# connectors.net
KiCad netlist of a schematic drawn in Altium Designer
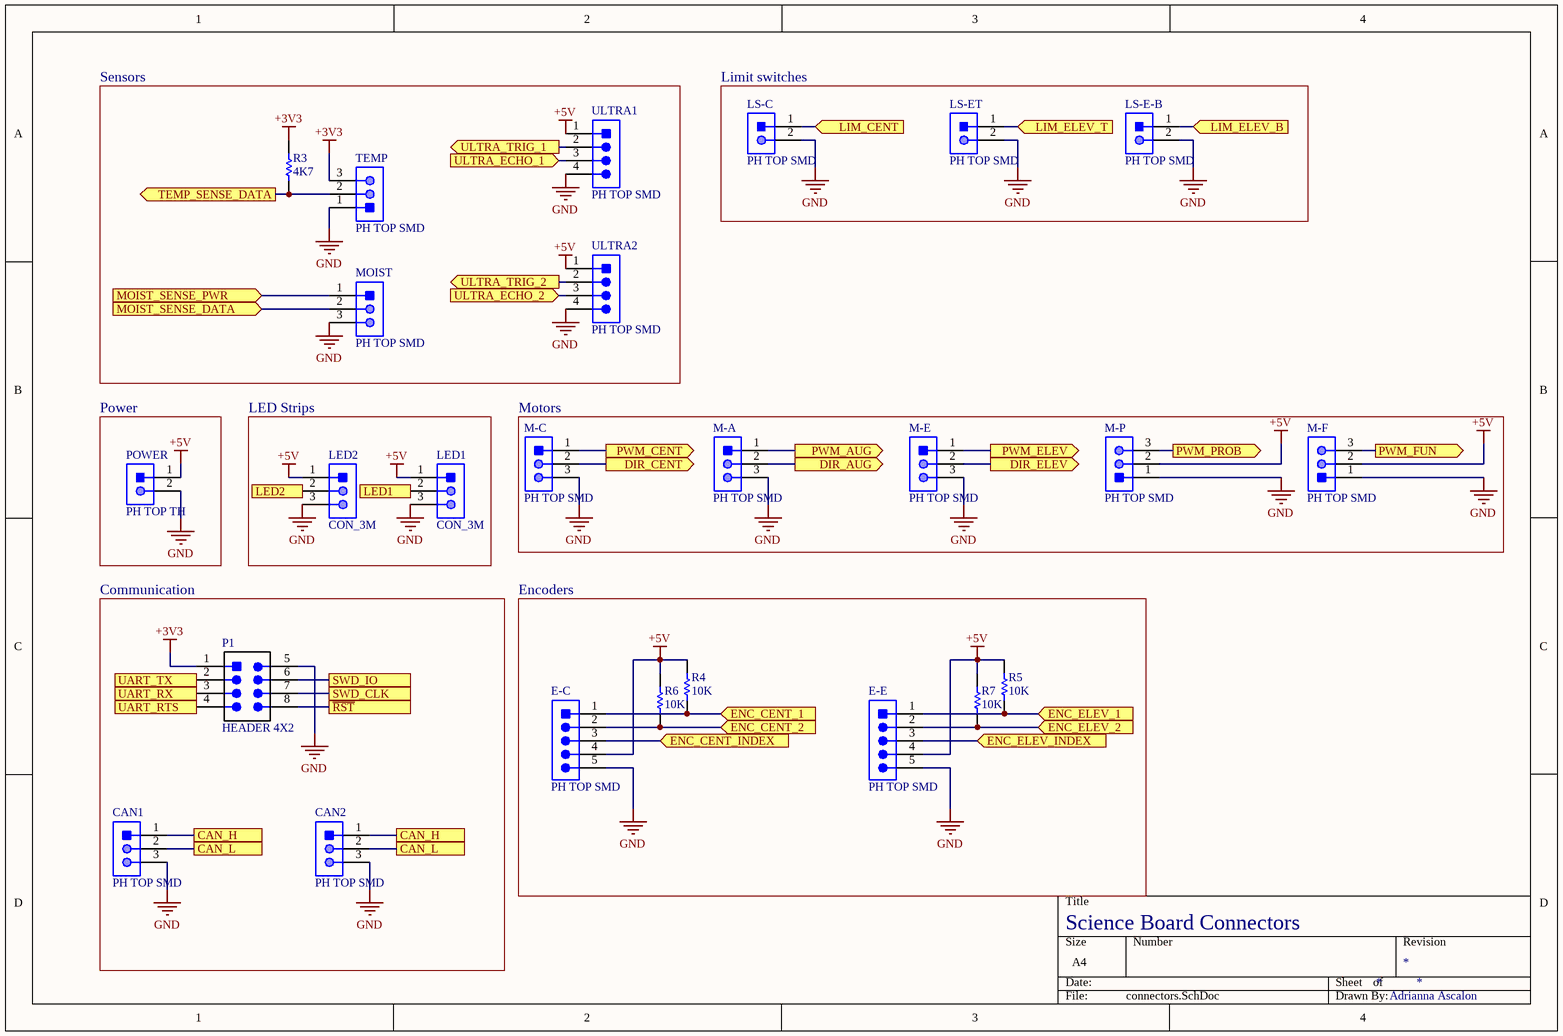
[diagram p0: connectors.SchDoc]

(export (version "E")
  (design (tool "Eeschema 10.0.6"))
  (components
    (comp (ref "CAN1")
      (value "PH TOP SMD")
      (footprint "JST-B3B-SM4-TB")
      (description "CONN HEADER PH TOP 3POS 2MM SMD")
      (fields (field (name "MANUFACTURER") "JST") (field (name "PART NUMBER") "B3B-PH-SM4-TB"))
      (libsource (lib "UWRT_Schematic_Library_2019") (part "CON_3M_PH_TOP_SMT"))
    )
    (comp (ref "CAN2")
      (value "PH TOP SMD")
      (footprint "JST-B3B-SM4-TB")
      (description "CONN HEADER PH TOP 3POS 2MM SMD")
      (fields (field (name "MANUFACTURER") "JST") (field (name "PART NUMBER") "B3B-PH-SM4-TB"))
      (libsource (lib "UWRT_Schematic_Library_2019") (part "CON_3M_PH_TOP_SMT"))
    )
    (comp (ref "E-C")
      (value "PH TOP SMD")
      (footprint "JST-B5B-SM4-TB")
      (description "CONN HEADER PH TOP 5POS 2MM SMD")
      (fields (field (name "MANUFACTURER") "JST") (field (name "PART NUMBER") "B5B-PH-SM4-TB"))
      (libsource (lib "UWRT_Schematic_Library_2019") (part "CON_5M_PH_TOP_SMT"))
    )
    (comp (ref "E-E")
      (value "PH TOP SMD")
      (footprint "JST-B5B-SM4-TB")
      (description "CONN HEADER PH TOP 5POS 2MM SMD")
      (fields (field (name "MANUFACTURER") "JST") (field (name "PART NUMBER") "B5B-PH-SM4-TB"))
      (libsource (lib "UWRT_Schematic_Library_2019") (part "CON_5M_PH_TOP_SMT"))
    )
    (comp (ref "LED1")
      (value "CON_3M")
      (footprint "JST-B3B-SM4-TB")
      (libsource (lib "UWRT_Schematic_Library_2019") (part "CON_3M"))
    )
    (comp (ref "LED2")
      (value "CON_3M")
      (footprint "JST-B3B-SM4-TB")
      (libsource (lib "UWRT_Schematic_Library_2019") (part "CON_3M"))
    )
    (comp (ref "LS-C")
      (value "PH TOP SMD")
      (footprint "JST-B2B-SM4-TB")
      (description "CONN HEADER PH TOP 2POS 2MM SMD")
      (fields (field (name "MANUFACTURER") "JST") (field (name "PART NUMBER") "B2B-PH-SM4-TB"))
      (libsource (lib "UWRT_Schematic_Library_2019") (part "CON_2M_PH_TOP_SMT"))
    )
    (comp (ref "LS-E-B")
      (value "PH TOP SMD")
      (footprint "JST-B2B-SM4-TB")
      (description "CONN HEADER PH TOP 2POS 2MM SMD")
      (fields (field (name "MANUFACTURER") "JST") (field (name "PART NUMBER") "B2B-PH-SM4-TB"))
      (libsource (lib "UWRT_Schematic_Library_2019") (part "CON_2M_PH_TOP_SMT"))
    )
    (comp (ref "LS-ET")
      (value "PH TOP SMD")
      (footprint "JST-B2B-SM4-TB")
      (description "CONN HEADER PH TOP 2POS 2MM SMD")
      (fields (field (name "MANUFACTURER") "JST") (field (name "PART NUMBER") "B2B-PH-SM4-TB"))
      (libsource (lib "UWRT_Schematic_Library_2019") (part "CON_2M_PH_TOP_SMT"))
    )
    (comp (ref "M-A")
      (value "PH TOP SMD")
      (footprint "JST-B3B-SM4-TB")
      (description "CONN HEADER PH TOP 3POS 2MM SMD")
      (fields (field (name "MANUFACTURER") "JST") (field (name "PART NUMBER") "B3B-PH-SM4-TB"))
      (libsource (lib "UWRT_Schematic_Library_2019") (part "CON_3M_PH_TOP_SMT"))
    )
    (comp (ref "M-C")
      (value "PH TOP SMD")
      (footprint "JST-B3B-SM4-TB")
      (description "CONN HEADER PH TOP 3POS 2MM SMD")
      (fields (field (name "MANUFACTURER") "JST") (field (name "PART NUMBER") "B3B-PH-SM4-TB"))
      (libsource (lib "UWRT_Schematic_Library_2019") (part "CON_3M_PH_TOP_SMT"))
    )
    (comp (ref "M-E")
      (value "PH TOP SMD")
      (footprint "JST-B3B-SM4-TB")
      (description "CONN HEADER PH TOP 3POS 2MM SMD")
      (fields (field (name "MANUFACTURER") "JST") (field (name "PART NUMBER") "B3B-PH-SM4-TB"))
      (libsource (lib "UWRT_Schematic_Library_2019") (part "CON_3M_PH_TOP_SMT"))
    )
    (comp (ref "M-F")
      (value "PH TOP SMD")
      (footprint "JST-B3B-SM4-TB")
      (description "CONN HEADER PH TOP 3POS 2MM SMD")
      (fields (field (name "MANUFACTURER") "JST") (field (name "PART NUMBER") "B3B-PH-SM4-TB"))
      (libsource (lib "") (part "CON_3M_PH_TOP_SMT_1"))
    )
    (comp (ref "M-P")
      (value "PH TOP SMD")
      (footprint "JST-B3B-SM4-TB")
      (description "CONN HEADER PH TOP 3POS 2MM SMD")
      (fields (field (name "MANUFACTURER") "JST") (field (name "PART NUMBER") "B3B-PH-SM4-TB"))
      (libsource (lib "") (part "CON_3M_PH_TOP_SMT_1"))
    )
    (comp (ref "MOIST")
      (value "PH TOP SMD")
      (footprint "JST-B3B-SM4-TB")
      (description "CONN HEADER PH TOP 3POS 2MM SMD")
      (fields (field (name "MANUFACTURER") "JST") (field (name "PART NUMBER") "B3B-PH-SM4-TB"))
      (libsource (lib "") (part "CON_3M_PH_TOP_SMT_2"))
    )
    (comp (ref "P1")
      (value "HEADER 4X2")
      (footprint "UWRT_Footprint_Library_2019:HEADER_2X4")
      (description "Header, 4-Pin Dual row")
      (fields (field (name "MPN") "GRPB042VWVN-RC") (field (name "DIGIKEY PART NUMBER") "S9015E-04-ND"))
      (libsource (lib "UWRT_Schematic_Library_2019") (part "HEADER 4X2"))
    )
    (comp (ref "POWER")
      (value "PH TOP TH")
      (footprint "JST-B2B-PHSK")
      (description "CONN HEADER PH TOP 2POS 2MM")
      (fields (field (name "MANUFACTURER") "JST") (field (name "PART NUMBER") "B2B-PH-K-S"))
      (libsource (lib "UWRT_Schematic_Library_2019") (part "CON_2M_PH_TOP_TH"))
    )
    (comp (ref "R3")
      (value "4K7")
      (footprint "RESC0603(1608)_N")
      (description "RES SMD 4.7K OHM 5% 1/10W 0603")
      (fields (field (name "MANUFACTURER") "Yageo") (field (name "TOLERANCE") "5%"))
      (libsource (lib "UWRT_Schematic_Library_2019") (part "RES_4K7_0603"))
    )
    (comp (ref "R4")
      (value "10K")
      (footprint "RESC0603(1608)_N")
      (description "RES SMD 10K OHM 5% 1/10W 0603")
      (fields (field (name "MANUFACTURER") "Yageo") (field (name "TOLERANCE") "5%"))
      (libsource (lib "UWRT_Schematic_Library_2019") (part "RES_10K_0603"))
    )
    (comp (ref "R5")
      (value "10K")
      (footprint "RESC0603(1608)_N")
      (description "RES SMD 10K OHM 5% 1/10W 0603")
      (fields (field (name "MANUFACTURER") "Yageo") (field (name "TOLERANCE") "5%"))
      (libsource (lib "UWRT_Schematic_Library_2019") (part "RES_10K_0603"))
    )
    (comp (ref "R6")
      (value "10K")
      (footprint "RESC0603(1608)_N")
      (description "RES SMD 10K OHM 5% 1/10W 0603")
      (fields (field (name "MANUFACTURER") "Yageo") (field (name "TOLERANCE") "5%"))
      (libsource (lib "UWRT_Schematic_Library_2019") (part "RES_10K_0603"))
    )
    (comp (ref "R7")
      (value "10K")
      (footprint "RESC0603(1608)_N")
      (description "RES SMD 10K OHM 5% 1/10W 0603")
      (fields (field (name "MANUFACTURER") "Yageo") (field (name "TOLERANCE") "5%"))
      (libsource (lib "UWRT_Schematic_Library_2019") (part "RES_10K_0603"))
    )
    (comp (ref "TEMP")
      (value "PH TOP SMD")
      (footprint "JST-B3B-SM4-TB")
      (description "CONN HEADER PH TOP 3POS 2MM SMD")
      (fields (field (name "MANUFACTURER") "JST") (field (name "PART NUMBER") "B3B-PH-SM4-TB"))
      (libsource (lib "") (part "CON_3M_PH_TOP_SMT_3"))
    )
    (comp (ref "ULTRA1")
      (value "PH TOP SMD")
      (footprint "JST-B4B-SM4-TB")
      (description "CONN HEADER PH TOP 4POS 2MM SMD")
      (fields (field (name "MANUFACTURER") "JST") (field (name "PART NUMBER") "B4B-PH-SM4-TB"))
      (libsource (lib "UWRT_Schematic_Library_2019") (part "CON_4M_PH_TOP_SMT"))
    )
    (comp (ref "ULTRA2")
      (value "PH TOP SMD")
      (footprint "JST-B4B-SM4-TB")
      (description "CONN HEADER PH TOP 4POS 2MM SMD")
      (fields (field (name "MANUFACTURER") "JST") (field (name "PART NUMBER") "B4B-PH-SM4-TB"))
      (libsource (lib "UWRT_Schematic_Library_2019") (part "CON_4M_PH_TOP_SMT"))
    )
  )
  (nets
    (net (code "1") (name "+3V3") (class "Default")
      (node (ref "P1") (pin "1") (pinfunction "VCC_1") (pintype "passive"))
      (node (ref "R3") (pin "2") (pinfunction "2_2") (pintype "passive"))
      (node (ref "TEMP") (pin "3") (pinfunction "3_3") (pintype "passive"))
    )
    (net (code "2") (name "+5V") (class "Default")
      (node (ref "E-C") (pin "4") (pinfunction "4_4") (pintype "passive"))
      (node (ref "E-E") (pin "4") (pinfunction "4_4") (pintype "passive"))
      (node (ref "LED1") (pin "1") (pinfunction "1_1") (pintype "passive"))
      (node (ref "LED2") (pin "1") (pinfunction "1_1") (pintype "passive"))
      (node (ref "M-F") (pin "2") (pinfunction "2_2") (pintype "passive"))
      (node (ref "M-P") (pin "2") (pinfunction "2_2") (pintype "passive"))
      (node (ref "POWER") (pin "1") (pinfunction "1_1") (pintype "passive"))
      (node (ref "R4") (pin "2") (pinfunction "2_2") (pintype "passive"))
      (node (ref "R5") (pin "2") (pinfunction "2_2") (pintype "passive"))
      (node (ref "R6") (pin "2") (pinfunction "2_2") (pintype "passive"))
      (node (ref "R7") (pin "2") (pinfunction "2_2") (pintype "passive"))
      (node (ref "ULTRA1") (pin "1") (pinfunction "1_1") (pintype "passive"))
      (node (ref "ULTRA2") (pin "1") (pinfunction "1_1") (pintype "passive"))
    )
    (net (code "3") (name "/CAN_H") (class "Default")
      (node (ref "CAN1") (pin "1") (pinfunction "1_1") (pintype "passive"))
      (node (ref "CAN2") (pin "1") (pinfunction "1_1") (pintype "passive"))
    )
    (net (code "4") (name "/CAN_L") (class "Default")
      (node (ref "CAN1") (pin "2") (pinfunction "2_2") (pintype "passive"))
      (node (ref "CAN2") (pin "2") (pinfunction "2_2") (pintype "passive"))
    )
    (net (code "5") (name "/DIR_AUG") (class "Default")
      (node (ref "M-A") (pin "2") (pinfunction "2_2") (pintype "passive"))
    )
    (net (code "6") (name "/DIR_CENT") (class "Default")
      (node (ref "M-C") (pin "2") (pinfunction "2_2") (pintype "passive"))
    )
    (net (code "7") (name "/DIR_ELEV") (class "Default")
      (node (ref "M-E") (pin "2") (pinfunction "2_2") (pintype "passive"))
    )
    (net (code "8") (name "/ENC_CENT_1") (class "Default")
      (node (ref "E-C") (pin "1") (pinfunction "1_1") (pintype "passive"))
      (node (ref "R4") (pin "1") (pinfunction "1_1") (pintype "passive"))
    )
    (net (code "9") (name "/ENC_CENT_2") (class "Default")
      (node (ref "E-C") (pin "2") (pinfunction "2_2") (pintype "passive"))
      (node (ref "R6") (pin "1") (pinfunction "1_1") (pintype "passive"))
    )
    (net (code "10") (name "/ENC_CENT_INDEX") (class "Default")
      (node (ref "E-C") (pin "3") (pinfunction "3_3") (pintype "passive"))
    )
    (net (code "11") (name "/ENC_ELEV_1") (class "Default")
      (node (ref "E-E") (pin "1") (pinfunction "1_1") (pintype "passive"))
      (node (ref "R5") (pin "1") (pinfunction "1_1") (pintype "passive"))
    )
    (net (code "12") (name "/ENC_ELEV_2") (class "Default")
      (node (ref "E-E") (pin "2") (pinfunction "2_2") (pintype "passive"))
      (node (ref "R7") (pin "1") (pinfunction "1_1") (pintype "passive"))
    )
    (net (code "13") (name "/ENC_ELEV_INDEX") (class "Default")
      (node (ref "E-E") (pin "3") (pinfunction "3_3") (pintype "passive"))
    )
    (net (code "14") (name "/LED1") (class "Default")
      (node (ref "LED1") (pin "2") (pinfunction "2_2") (pintype "passive"))
    )
    (net (code "15") (name "/LED2") (class "Default")
      (node (ref "LED2") (pin "2") (pinfunction "2_2") (pintype "passive"))
    )
    (net (code "16") (name "/LIM_CENT") (class "Default")
      (node (ref "LS-C") (pin "1") (pinfunction "1_1") (pintype "passive"))
    )
    (net (code "17") (name "/LIM_ELEV_B") (class "Default")
      (node (ref "LS-E-B") (pin "1") (pinfunction "1_1") (pintype "passive"))
    )
    (net (code "18") (name "/LIM_ELEV_T") (class "Default")
      (node (ref "LS-ET") (pin "1") (pinfunction "1_1") (pintype "passive"))
    )
    (net (code "19") (name "/MOIST_SENSE_DATA") (class "Default")
      (node (ref "MOIST") (pin "2") (pinfunction "2_2") (pintype "passive"))
    )
    (net (code "20") (name "/MOIST_SENSE_PWR") (class "Default")
      (node (ref "MOIST") (pin "1") (pinfunction "1_1") (pintype "passive"))
    )
    (net (code "21") (name "/PWM_AUG") (class "Default")
      (node (ref "M-A") (pin "1") (pinfunction "1_1") (pintype "passive"))
    )
    (net (code "22") (name "/PWM_CENT") (class "Default")
      (node (ref "M-C") (pin "1") (pinfunction "1_1") (pintype "passive"))
    )
    (net (code "23") (name "/PWM_ELEV") (class "Default")
      (node (ref "M-E") (pin "1") (pinfunction "1_1") (pintype "passive"))
    )
    (net (code "24") (name "/PWM_FUN") (class "Default")
      (node (ref "M-F") (pin "3") (pinfunction "3_3") (pintype "passive"))
    )
    (net (code "25") (name "/PWM_PROB") (class "Default")
      (node (ref "M-P") (pin "3") (pinfunction "3_3") (pintype "passive"))
    )
    (net (code "26") (name "/SWD_CLK") (class "Default")
      (node (ref "P1") (pin "7") (pinfunction "3_7") (pintype "passive"))
    )
    (net (code "27") (name "/SWD_IO") (class "Default")
      (node (ref "P1") (pin "6") (pinfunction "2_6") (pintype "passive"))
    )
    (net (code "28") (name "/TEMP_SENSE_DATA") (class "Default")
      (node (ref "R3") (pin "1") (pinfunction "1_1") (pintype "passive"))
      (node (ref "TEMP") (pin "2") (pinfunction "2_2") (pintype "passive"))
    )
    (net (code "29") (name "/UART_RTS") (class "Default")
      (node (ref "P1") (pin "4") (pinfunction "4_4") (pintype "passive"))
    )
    (net (code "30") (name "/UART_RX") (class "Default")
      (node (ref "P1") (pin "3") (pinfunction "3_3") (pintype "passive"))
    )
    (net (code "31") (name "/UART_TX") (class "Default")
      (node (ref "P1") (pin "2") (pinfunction "2_2") (pintype "passive"))
    )
    (net (code "32") (name "/ULTRA_ECHO_1") (class "Default")
      (node (ref "ULTRA1") (pin "3") (pinfunction "3_3") (pintype "passive"))
    )
    (net (code "33") (name "/ULTRA_ECHO_2") (class "Default")
      (node (ref "ULTRA2") (pin "3") (pinfunction "3_3") (pintype "passive"))
    )
    (net (code "34") (name "/ULTRA_TRIG_1") (class "Default")
      (node (ref "ULTRA1") (pin "2") (pinfunction "2_2") (pintype "passive"))
    )
    (net (code "35") (name "/ULTRA_TRIG_2") (class "Default")
      (node (ref "ULTRA2") (pin "2") (pinfunction "2_2") (pintype "passive"))
    )
    (net (code "36") (name "/~{RST}") (class "Default")
      (node (ref "P1") (pin "8") (pinfunction "4_8") (pintype "passive"))
    )
    (net (code "37") (name "GND") (class "Default")
      (node (ref "CAN1") (pin "3") (pinfunction "3_3") (pintype "passive"))
      (node (ref "CAN2") (pin "3") (pinfunction "3_3") (pintype "passive"))
      (node (ref "E-C") (pin "5") (pinfunction "5_5") (pintype "passive"))
      (node (ref "E-E") (pin "5") (pinfunction "5_5") (pintype "passive"))
      (node (ref "LED1") (pin "3") (pinfunction "3_3") (pintype "passive"))
      (node (ref "LED2") (pin "3") (pinfunction "3_3") (pintype "passive"))
      (node (ref "LS-C") (pin "2") (pinfunction "2_2") (pintype "passive"))
      (node (ref "LS-E-B") (pin "2") (pinfunction "2_2") (pintype "passive"))
      (node (ref "LS-ET") (pin "2") (pinfunction "2_2") (pintype "passive"))
      (node (ref "M-A") (pin "3") (pinfunction "3_3") (pintype "passive"))
      (node (ref "M-C") (pin "3") (pinfunction "3_3") (pintype "passive"))
      (node (ref "M-E") (pin "3") (pinfunction "3_3") (pintype "passive"))
      (node (ref "M-F") (pin "1") (pinfunction "1_1") (pintype "passive"))
      (node (ref "M-P") (pin "1") (pinfunction "1_1") (pintype "passive"))
      (node (ref "MOIST") (pin "3") (pinfunction "3_3") (pintype "passive"))
      (node (ref "P1") (pin "5") (pinfunction "GND_5") (pintype "passive"))
      (node (ref "POWER") (pin "2") (pinfunction "2_2") (pintype "passive"))
      (node (ref "TEMP") (pin "1") (pinfunction "1_1") (pintype "passive"))
      (node (ref "ULTRA1") (pin "4") (pinfunction "4_4") (pintype "passive"))
      (node (ref "ULTRA2") (pin "4") (pinfunction "4_4") (pintype "passive"))
    )
  )
)
